# FLASH.net
KiCad netlist of a schematic drawn in Altium Designer
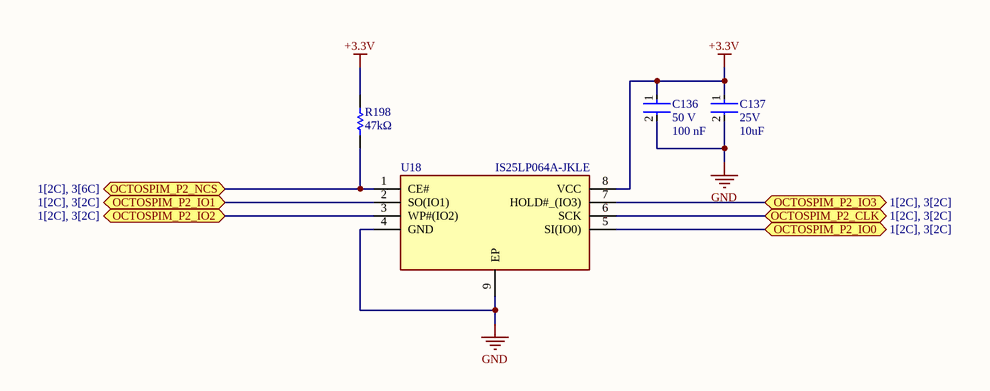
[diagram p0: FLASH.SchDoc]

(export (version "E")
  (design (tool "Eeschema 10.0.6"))
  (components
    (comp (ref "C136")
      (value "100 nF")
      (footprint "FP-C0603C-CF-IPC_B")
      (description "CAP CER 0.1UF 50V 20% X7R 0603")
      (fields
        (field (name "VOLTAGE RATING") "50 V")
        (field (name "MANUFACTURER PART NUMBER") "C0603C104M5RACTU")
        (field (name "MANUFACTURER") "KEMET")
      )
      (libsource (lib "Altium Content Vault") (part "b4654b650e69147ec39a6b967a45e02"))
    )
    (comp (ref "C137")
      (value "C1608X5R1E106M080AC")
      (footprint "FP-C1608-080-IPC_B")
      (description "CAP CER 10UF 25V X5R 0603")
      (fields
        (field (name "VOLTAGE RATING") "25V")
        (field (name "TOLERANCE") "20%")
        (field (name "CAPACITANCE") "10uF")
      )
      (libsource (lib "Altium Content Vault") (part "11868f565c42a9108669ba33697ecf6"))
    )
    (comp (ref "R198")
      (value "RC0603FR-1347KL")
      (footprint "RESC1608X55X25ML10T15")
      (fields (field (name "MANUFACTURER") "Yageo") (field (name "RESISTANCE") "47kΩ"))
      (libsource (lib "Altium Content Vault") (part "RES"))
    )
    (comp (ref "U18")
      (value "IS25LP064A-JKLE")
      (footprint "SamacSys:SON127P600X500X80-9N-D")
      (description "Integrated Circuit")
      (libsource (lib "*") (part "IS25LP064A-JKLE"))
    )
  )
  (nets
    (net (code "1") (name "+3.3V") (class "Default")
      (node (ref "C136") (pin "1") (pinfunction "1_1") (pintype "passive"))
      (node (ref "C137") (pin "1") (pinfunction "1_1") (pintype "passive"))
      (node (ref "R198") (pin "2") (pinfunction "2_2") (pintype "passive"))
      (node (ref "U18") (pin "8") (pinfunction "VCC_8") (pintype "passive"))
    )
    (net (code "2") (name "/OCTOSPIM_P2_CLK") (class "Default")
      (node (ref "U18") (pin "6") (pinfunction "SCK_6") (pintype "passive"))
    )
    (net (code "3") (name "/OCTOSPIM_P2_IO0") (class "Default")
      (node (ref "U18") (pin "5") (pinfunction "SI(IO0)_5") (pintype "passive"))
    )
    (net (code "4") (name "/OCTOSPIM_P2_IO1") (class "Default")
      (node (ref "U18") (pin "2") (pinfunction "SO(IO1)_2") (pintype "passive"))
    )
    (net (code "5") (name "/OCTOSPIM_P2_IO2") (class "Default")
      (node (ref "U18") (pin "3") (pinfunction "WP#(IO2)_3") (pintype "passive"))
    )
    (net (code "6") (name "/OCTOSPIM_P2_IO3") (class "Default")
      (node (ref "U18") (pin "7") (pinfunction "HOLD#_(IO3)_7") (pintype "passive"))
    )
    (net (code "7") (name "/OCTOSPIM_P2_NCS") (class "Default")
      (node (ref "R198") (pin "1") (pinfunction "1_1") (pintype "passive"))
      (node (ref "U18") (pin "1") (pinfunction "CE#_1") (pintype "passive"))
    )
    (net (code "8") (name "GND") (class "Default")
      (node (ref "C136") (pin "2") (pinfunction "2_2") (pintype "passive"))
      (node (ref "C137") (pin "2") (pinfunction "2_2") (pintype "passive"))
      (node (ref "U18") (pin "4") (pinfunction "GND_4") (pintype "passive"))
      (node (ref "U18") (pin "9") (pinfunction "EP_9") (pintype "passive"))
    )
  )
)
